# AT45DB041ESHNB.net
KiCad netlist of a schematic drawn in EAGLE
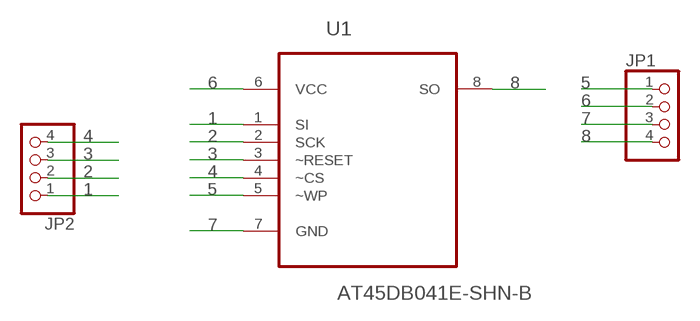
[diagram p0: schematic, sheet 1]

(export (version "E")
  (design (tool "Eeschema 10.0.6"))
  (components
    (comp (ref "JP1")
      (value "PINHD-1X4")
      (footprint "eagle-import:1X04")
      (libsource (lib "eagle-import") (part "PINHD-1X4"))
    )
    (comp (ref "JP2")
      (value "PINHD-1X4")
      (footprint "eagle-import:1X04")
      (libsource (lib "eagle-import") (part "PINHD-1X4"))
    )
    (comp (ref "U1")
      (value "AT45DB041E-SHN-B")
      (footprint "eagle-import:SOIC127P798X216-8N")
      (fields (field (name "MF") "Adesto"))
      (libsource (lib "eagle-import") (part "AT45DB041E-SHN-B"))
    )
  )
  (nets
    (net (code "1") (name "/1") (class "Default")
      (node (ref "JP2") (pin "1") (pinfunction "1_1") (pintype "passive"))
      (node (ref "U1") (pin "1") (pinfunction "SI_1") (pintype "input"))
    )
    (net (code "2") (name "/2") (class "Default")
      (node (ref "JP2") (pin "2") (pinfunction "2_2") (pintype "passive"))
      (node (ref "U1") (pin "2") (pinfunction "SCK_2") (pintype "input"))
    )
    (net (code "3") (name "/3") (class "Default")
      (node (ref "JP2") (pin "3") (pinfunction "3_3") (pintype "passive"))
      (node (ref "U1") (pin "3") (pinfunction "~{RESET}_3") (pintype "input"))
    )
    (net (code "4") (name "/4") (class "Default")
      (node (ref "JP2") (pin "4") (pinfunction "4_4") (pintype "passive"))
      (node (ref "U1") (pin "4") (pinfunction "~{CS}_4") (pintype "input"))
    )
    (net (code "5") (name "/5") (class "Default")
      (node (ref "JP1") (pin "1") (pinfunction "1_1") (pintype "passive"))
      (node (ref "U1") (pin "5") (pinfunction "~{WP}_5") (pintype "input"))
    )
    (net (code "6") (name "/6") (class "Default")
      (node (ref "JP1") (pin "2") (pinfunction "2_2") (pintype "passive"))
      (node (ref "U1") (pin "6") (pinfunction "VCC_6") (pintype "power_in"))
    )
    (net (code "7") (name "/7") (class "Default")
      (node (ref "JP1") (pin "3") (pinfunction "3_3") (pintype "passive"))
      (node (ref "U1") (pin "7") (pinfunction "GND_7") (pintype "passive"))
    )
    (net (code "8") (name "/8") (class "Default")
      (node (ref "JP1") (pin "4") (pinfunction "4_4") (pintype "passive"))
      (node (ref "U1") (pin "8") (pinfunction "SO_8") (pintype "output"))
    )
  )
)
